# board.net
KiCad netlist of a schematic drawn in EAGLE
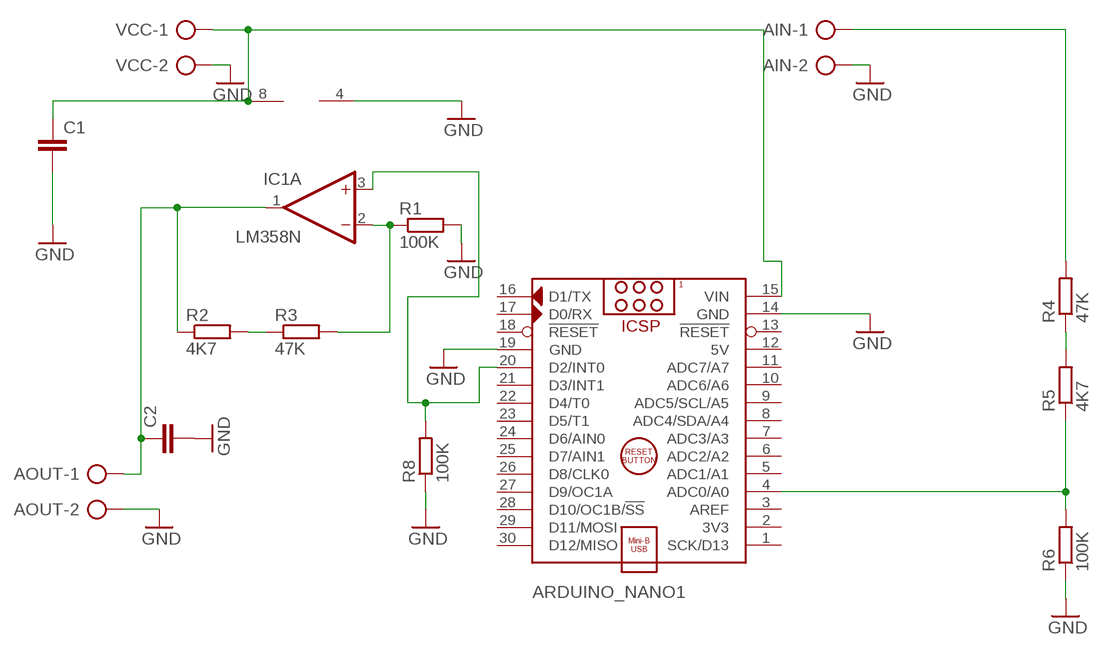
[diagram p0: schematic, sheet 1]

(export (version "E")
  (design (tool "Eeschema 10.0.6"))
  (components
    (comp (ref "AIN")
      (value "AK300/2")
      (footprint "eagle-import:AK300_2")
      (libsource (lib "eagle-import") (part "AK300/2"))
    )
    (comp (ref "AOUT")
      (value "AK300/2")
      (footprint "eagle-import:AK300_2")
      (libsource (lib "eagle-import") (part "AK300/2"))
    )
    (comp (ref "ARDUINO_NANO1")
      (value "ARDUINO_NANO")
      (footprint "eagle-import:ARDUINO_NANO")
      (libsource (lib "eagle-import") (part "ARDUINO_NANO"))
    )
    (comp (ref "C1")
      (value "C5/5")
      (footprint "eagle-import:C5B5")
      (libsource (lib "eagle-import") (part "C5/5"))
    )
    (comp (ref "C2")
      (value "C5/5")
      (footprint "eagle-import:C5B5")
      (libsource (lib "eagle-import") (part "C5/5"))
    )
    (comp (ref "IC1")
      (value "LM358N")
      (footprint "eagle-import:DIL08")
      (libsource (lib "eagle-import") (part "LM358N"))
    )
    (comp (ref "R1")
      (value "100K")
      (footprint "eagle-import:0207_10")
      (libsource (lib "eagle-import") (part "R-EU_0207/10"))
    )
    (comp (ref "R2")
      (value "4K7")
      (footprint "eagle-import:0207_10")
      (libsource (lib "eagle-import") (part "R-EU_0207/10"))
    )
    (comp (ref "R3")
      (value "47K")
      (footprint "eagle-import:0207_10")
      (libsource (lib "eagle-import") (part "R-EU_0207/10"))
    )
    (comp (ref "R4")
      (value "47K")
      (footprint "eagle-import:0207_10")
      (libsource (lib "eagle-import") (part "R-EU_0207/10"))
    )
    (comp (ref "R5")
      (value "4K7")
      (footprint "eagle-import:0207_10")
      (libsource (lib "eagle-import") (part "R-EU_0207/10"))
    )
    (comp (ref "R6")
      (value "100K")
      (footprint "eagle-import:0207_10")
      (libsource (lib "eagle-import") (part "R-EU_0207/10"))
    )
    (comp (ref "R8")
      (value "100K")
      (footprint "eagle-import:0207_10")
      (libsource (lib "eagle-import") (part "R-EU_0207/10"))
    )
    (comp (ref "VCC")
      (value "AK300/2")
      (footprint "eagle-import:AK300_2")
      (libsource (lib "eagle-import") (part "AK300/2"))
    )
  )
  (nets
    (net (code "1") (name "/5V") (class "Default")
      (node (ref "ARDUINO_NANO1") (pin "12") (pinfunction "5V_12") (pintype "power_in"))
    )
    (net (code "2") (name "GND") (class "Default")
      (node (ref "AIN") (pin "2") (pinfunction "KL_2") (pintype "passive"))
      (node (ref "AOUT") (pin "2") (pinfunction "KL_2") (pintype "passive"))
      (node (ref "ARDUINO_NANO1") (pin "14") (pinfunction "GND_14") (pintype "power_in"))
      (node (ref "ARDUINO_NANO1") (pin "19") (pinfunction "GND_19") (pintype "power_in"))
      (node (ref "C1") (pin "2") (pinfunction "2_2") (pintype "passive"))
      (node (ref "C2") (pin "2") (pinfunction "2_2") (pintype "passive"))
      (node (ref "IC1") (pin "4") (pinfunction "V-_4") (pintype "power_in"))
      (node (ref "R1") (pin "2") (pinfunction "2_2") (pintype "passive"))
      (node (ref "R6") (pin "1") (pinfunction "1_1") (pintype "passive"))
      (node (ref "R8") (pin "1") (pinfunction "1_1") (pintype "passive"))
      (node (ref "VCC") (pin "2") (pinfunction "KL_2") (pintype "passive"))
    )
    (net (code "3") (name "Net-(AINA-KL)") (class "Default")
      (node (ref "AIN") (pin "1") (pinfunction "KL_1") (pintype "passive"))
      (node (ref "R4") (pin "2") (pinfunction "2_2") (pintype "passive"))
    )
    (net (code "4") (name "Net-(AOUTA-KL)") (class "Default")
      (node (ref "AOUT") (pin "1") (pinfunction "KL_1") (pintype "passive"))
      (node (ref "C2") (pin "1") (pinfunction "1_1") (pintype "passive"))
      (node (ref "IC1") (pin "1") (pinfunction "OUT_1") (pintype "output"))
      (node (ref "R2") (pin "1") (pinfunction "1_1") (pintype "passive"))
    )
    (net (code "5") (name "Net-(ARDUINO_NANO1-ADC0{slash}A0)") (class "Default")
      (node (ref "ARDUINO_NANO1") (pin "4") (pinfunction "ADC0/A0_4") (pintype "bidirectional"))
      (node (ref "R5") (pin "1") (pinfunction "1_1") (pintype "passive"))
      (node (ref "R6") (pin "2") (pinfunction "2_2") (pintype "passive"))
    )
    (net (code "6") (name "Net-(ARDUINO_NANO1-D2{slash}INT0)") (class "Default")
      (node (ref "ARDUINO_NANO1") (pin "20") (pinfunction "D2/INT0_20") (pintype "bidirectional"))
      (node (ref "IC1") (pin "3") (pinfunction "+IN_3") (pintype "input"))
      (node (ref "R8") (pin "2") (pinfunction "2_2") (pintype "passive"))
    )
    (net (code "7") (name "Net-(ARDUINO_NANO1-VIN)") (class "Default")
      (node (ref "ARDUINO_NANO1") (pin "15") (pinfunction "VIN_15") (pintype "power_in"))
      (node (ref "C1") (pin "1") (pinfunction "1_1") (pintype "passive"))
      (node (ref "IC1") (pin "8") (pinfunction "V+_8") (pintype "power_in"))
      (node (ref "VCC") (pin "1") (pinfunction "KL_1") (pintype "passive"))
    )
    (net (code "8") (name "Net-(IC1A--IN)") (class "Default")
      (node (ref "IC1") (pin "2") (pinfunction "-IN_2") (pintype "input"))
      (node (ref "R1") (pin "1") (pinfunction "1_1") (pintype "passive"))
      (node (ref "R3") (pin "2") (pinfunction "2_2") (pintype "passive"))
    )
    (net (code "9") (name "Net-(R2-Pad2)") (class "Default")
      (node (ref "R2") (pin "2") (pinfunction "2_2") (pintype "passive"))
      (node (ref "R3") (pin "1") (pinfunction "1_1") (pintype "passive"))
    )
    (net (code "10") (name "Net-(R4-Pad1)") (class "Default")
      (node (ref "R4") (pin "1") (pinfunction "1_1") (pintype "passive"))
      (node (ref "R5") (pin "2") (pinfunction "2_2") (pintype "passive"))
    )
    (net (code "11") (name "unconnected-(ARDUINO_NANO1-3V3-Pad2)") (class "Default")
      (node (ref "ARDUINO_NANO1") (pin "2") (pinfunction "3V3_2") (pintype "output"))
    )
    (net (code "12") (name "unconnected-(ARDUINO_NANO1-ADC1{slash}A1-Pad5)") (class "Default")
      (node (ref "ARDUINO_NANO1") (pin "5") (pinfunction "ADC1/A1_5") (pintype "bidirectional"))
    )
    (net (code "13") (name "unconnected-(ARDUINO_NANO1-ADC2{slash}A2-Pad6)") (class "Default")
      (node (ref "ARDUINO_NANO1") (pin "6") (pinfunction "ADC2/A2_6") (pintype "bidirectional"))
    )
    (net (code "14") (name "unconnected-(ARDUINO_NANO1-ADC3{slash}A3-Pad7)") (class "Default")
      (node (ref "ARDUINO_NANO1") (pin "7") (pinfunction "ADC3/A3_7") (pintype "bidirectional"))
    )
    (net (code "15") (name "unconnected-(ARDUINO_NANO1-ADC4{slash}SDA{slash}A4-Pad8)") (class "Default")
      (node (ref "ARDUINO_NANO1") (pin "8") (pinfunction "ADC4/SDA/A4_8") (pintype "bidirectional"))
    )
    (net (code "16") (name "unconnected-(ARDUINO_NANO1-ADC5{slash}SCL{slash}A5-Pad9)") (class "Default")
      (node (ref "ARDUINO_NANO1") (pin "9") (pinfunction "ADC5/SCL/A5_9") (pintype "bidirectional"))
    )
    (net (code "17") (name "unconnected-(ARDUINO_NANO1-ADC6{slash}A6-Pad10)") (class "Default")
      (node (ref "ARDUINO_NANO1") (pin "10") (pinfunction "ADC6/A6_10") (pintype "bidirectional"))
    )
    (net (code "18") (name "unconnected-(ARDUINO_NANO1-ADC7{slash}A7-Pad11)") (class "Default")
      (node (ref "ARDUINO_NANO1") (pin "11") (pinfunction "ADC7/A7_11") (pintype "bidirectional"))
    )
    (net (code "19") (name "unconnected-(ARDUINO_NANO1-AREF-Pad3)") (class "Default")
      (node (ref "ARDUINO_NANO1") (pin "3") (pinfunction "AREF_3") (pintype "input"))
    )
    (net (code "20") (name "unconnected-(ARDUINO_NANO1-D0{slash}RX-Pad17)") (class "Default")
      (node (ref "ARDUINO_NANO1") (pin "17") (pinfunction "D0/RX_17") (pintype "bidirectional"))
    )
    (net (code "21") (name "unconnected-(ARDUINO_NANO1-D1{slash}TX-Pad16)") (class "Default")
      (node (ref "ARDUINO_NANO1") (pin "16") (pinfunction "D1/TX_16") (pintype "bidirectional"))
    )
    (net (code "22") (name "unconnected-(ARDUINO_NANO1-D3{slash}INT1-Pad21)") (class "Default")
      (node (ref "ARDUINO_NANO1") (pin "21") (pinfunction "D3/INT1_21") (pintype "bidirectional"))
    )
    (net (code "23") (name "unconnected-(ARDUINO_NANO1-D4{slash}T0-Pad22)") (class "Default")
      (node (ref "ARDUINO_NANO1") (pin "22") (pinfunction "D4/T0_22") (pintype "bidirectional"))
    )
    (net (code "24") (name "unconnected-(ARDUINO_NANO1-D5{slash}T1-Pad23)") (class "Default")
      (node (ref "ARDUINO_NANO1") (pin "23") (pinfunction "D5/T1_23") (pintype "bidirectional"))
    )
    (net (code "25") (name "unconnected-(ARDUINO_NANO1-D6{slash}AIN0-Pad24)") (class "Default")
      (node (ref "ARDUINO_NANO1") (pin "24") (pinfunction "D6/AIN0_24") (pintype "bidirectional"))
    )
    (net (code "26") (name "unconnected-(ARDUINO_NANO1-D7{slash}AIN1-Pad25)") (class "Default")
      (node (ref "ARDUINO_NANO1") (pin "25") (pinfunction "D7/AIN1_25") (pintype "bidirectional"))
    )
    (net (code "27") (name "unconnected-(ARDUINO_NANO1-D8{slash}CLK0-Pad26)") (class "Default")
      (node (ref "ARDUINO_NANO1") (pin "26") (pinfunction "D8/CLK0_26") (pintype "bidirectional"))
    )
    (net (code "28") (name "unconnected-(ARDUINO_NANO1-D9{slash}OC1A-Pad27)") (class "Default")
      (node (ref "ARDUINO_NANO1") (pin "27") (pinfunction "D9/OC1A_27") (pintype "bidirectional"))
    )
    (net (code "29") (name "unconnected-(ARDUINO_NANO1-D10{slash}OC1B{slash}~{SS}-Pad28)") (class "Default")
      (node (ref "ARDUINO_NANO1") (pin "28") (pinfunction "D10/OC1B/~{SS}_28") (pintype "bidirectional"))
    )
    (net (code "30") (name "unconnected-(ARDUINO_NANO1-D11{slash}MOSI-Pad29)") (class "Default")
      (node (ref "ARDUINO_NANO1") (pin "29") (pinfunction "D11/MOSI_29") (pintype "bidirectional"))
    )
    (net (code "31") (name "unconnected-(ARDUINO_NANO1-D12{slash}MISO-Pad30)") (class "Default")
      (node (ref "ARDUINO_NANO1") (pin "30") (pinfunction "D12/MISO_30") (pintype "bidirectional"))
    )
    (net (code "32") (name "unconnected-(ARDUINO_NANO1-SCK{slash}D13-Pad1)") (class "Default")
      (node (ref "ARDUINO_NANO1") (pin "1") (pinfunction "SCK/D13_1") (pintype "bidirectional"))
    )
    (net (code "33") (name "unconnected-(ARDUINO_NANO1-~{RESET}-Pad13)") (class "Default")
      (node (ref "ARDUINO_NANO1") (pin "13") (pinfunction "~{RESET}_13") (pintype "input"))
    )
    (net (code "34") (name "unconnected-(ARDUINO_NANO1-~{RESET}-Pad18)") (class "Default")
      (node (ref "ARDUINO_NANO1") (pin "18") (pinfunction "~{RESET}_18") (pintype "input"))
    )
  )
)
